# JTAG_BUFFER.net
KiCad netlist of a schematic drawn in Altium Designer
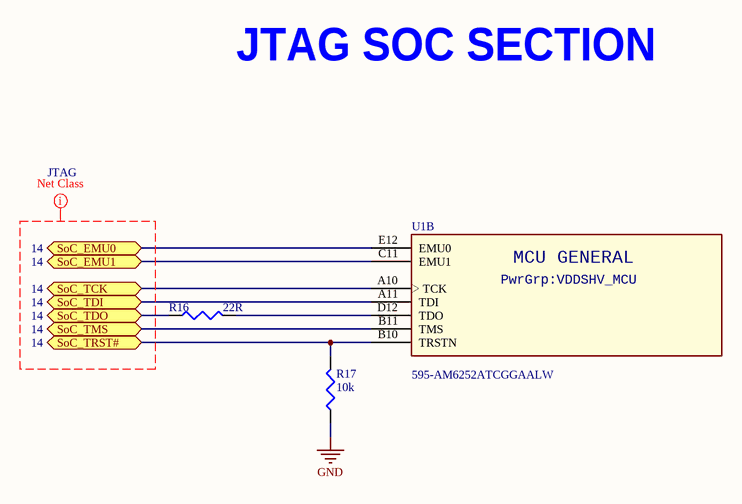
[diagram p0: JTAG BUFFER.SchDoc]

(export (version "E")
  (design (tool "Eeschema 10.0.6"))
  (components
    (comp (ref "R16")
      (value "22R")
      (footprint "R0402")
      (description "RES 22.0 OHM 1/16W 1% 0402 SMD")
      (fields
        (field (name "MANUFACTURER") "Yageo")
        (field (name "MANUFACTURER PART NUMBER") "RC0402FR-0722RL")
      )
      (libsource (lib "Schlib AM625") (part "RC0402FR-0722RL"))
    )
    (comp (ref "R17")
      (value "10k")
      (footprint "R0201")
      (description "RES 10K OHM 1/20W 1% 0201 SMD")
      (fields
        (field (name "MANUFACTURER") "Yageo")
        (field (name "MANUFACTURER PART NUMBER") "RC0201FR-0710KL")
        (field (name ".CREATOR") "MM")
        (field (name ".CHECKED PCB") "MM")
        (field (name ".CHECKED SCH") "MM")
      )
      (libsource (lib "Schlib AM625") (part "RC0201FR-0710KL"))
    )
    (comp (ref "U1")
      (value "AM62-EVM_BGA425")
      (footprint "BGA425C50P25X25_1300X1300X89")
      (description "ARM® Cortex®-A53 Microprocessor IC Sitara™ 2 Core, 64-Bit 1.4GHz 425-FCCSP (13x13)")
      (fields
        (field (name "MANUFACTURER") "Texas Instruments")
        (field (name "MANUFACTURER PART NUMBER") "AM6252ATCGGAALW")
        (field (name "SUPPLIER PART NUMBER 1") "595-AM6252ATCGGAALW")
      )
      (libsource (lib "Schlib AM625") (part "AM62-EVM_BGA425"))
    )
  )
  (nets
    (net (code "1") (name "/SoC_EMU0") (class "Default")
      (node (ref "U1") (pin "E12") (pinfunction "EMU0_E12") (pintype "passive"))
    )
    (net (code "2") (name "/SoC_EMU1") (class "Default")
      (node (ref "U1") (pin "C11") (pinfunction "EMU1_C11") (pintype "passive"))
    )
    (net (code "3") (name "/SoC_TCK") (class "Default")
      (node (ref "U1") (pin "A10") (pinfunction "TCK_A10") (pintype "passive"))
    )
    (net (code "4") (name "/SoC_TDI") (class "Default")
      (node (ref "U1") (pin "A11") (pinfunction "TDI_A11") (pintype "passive"))
    )
    (net (code "5") (name "/SoC_TDO") (class "Default")
      (node (ref "R16") (pin "1") (pinfunction "1_1") (pintype "passive"))
    )
    (net (code "6") (name "/SoC_TMS") (class "Default")
      (node (ref "U1") (pin "B11") (pinfunction "TMS_B11") (pintype "passive"))
    )
    (net (code "7") (name "/SoC_TRST#") (class "Default")
      (node (ref "R17") (pin "2") (pinfunction "2_2") (pintype "passive"))
      (node (ref "U1") (pin "B10") (pinfunction "TRSTN_B10") (pintype "passive"))
    )
    (net (code "8") (name "GND") (class "Default")
      (node (ref "R17") (pin "1") (pinfunction "1_1") (pintype "passive"))
    )
    (net (code "9") (name "Net-(U1B-TDO)") (class "Default")
      (node (ref "R16") (pin "2") (pinfunction "2_2") (pintype "passive"))
      (node (ref "U1") (pin "D12") (pinfunction "TDO_D12") (pintype "passive"))
    )
  )
)
